# Main_Sch.net
KiCad netlist of a schematic drawn in Altium Designer
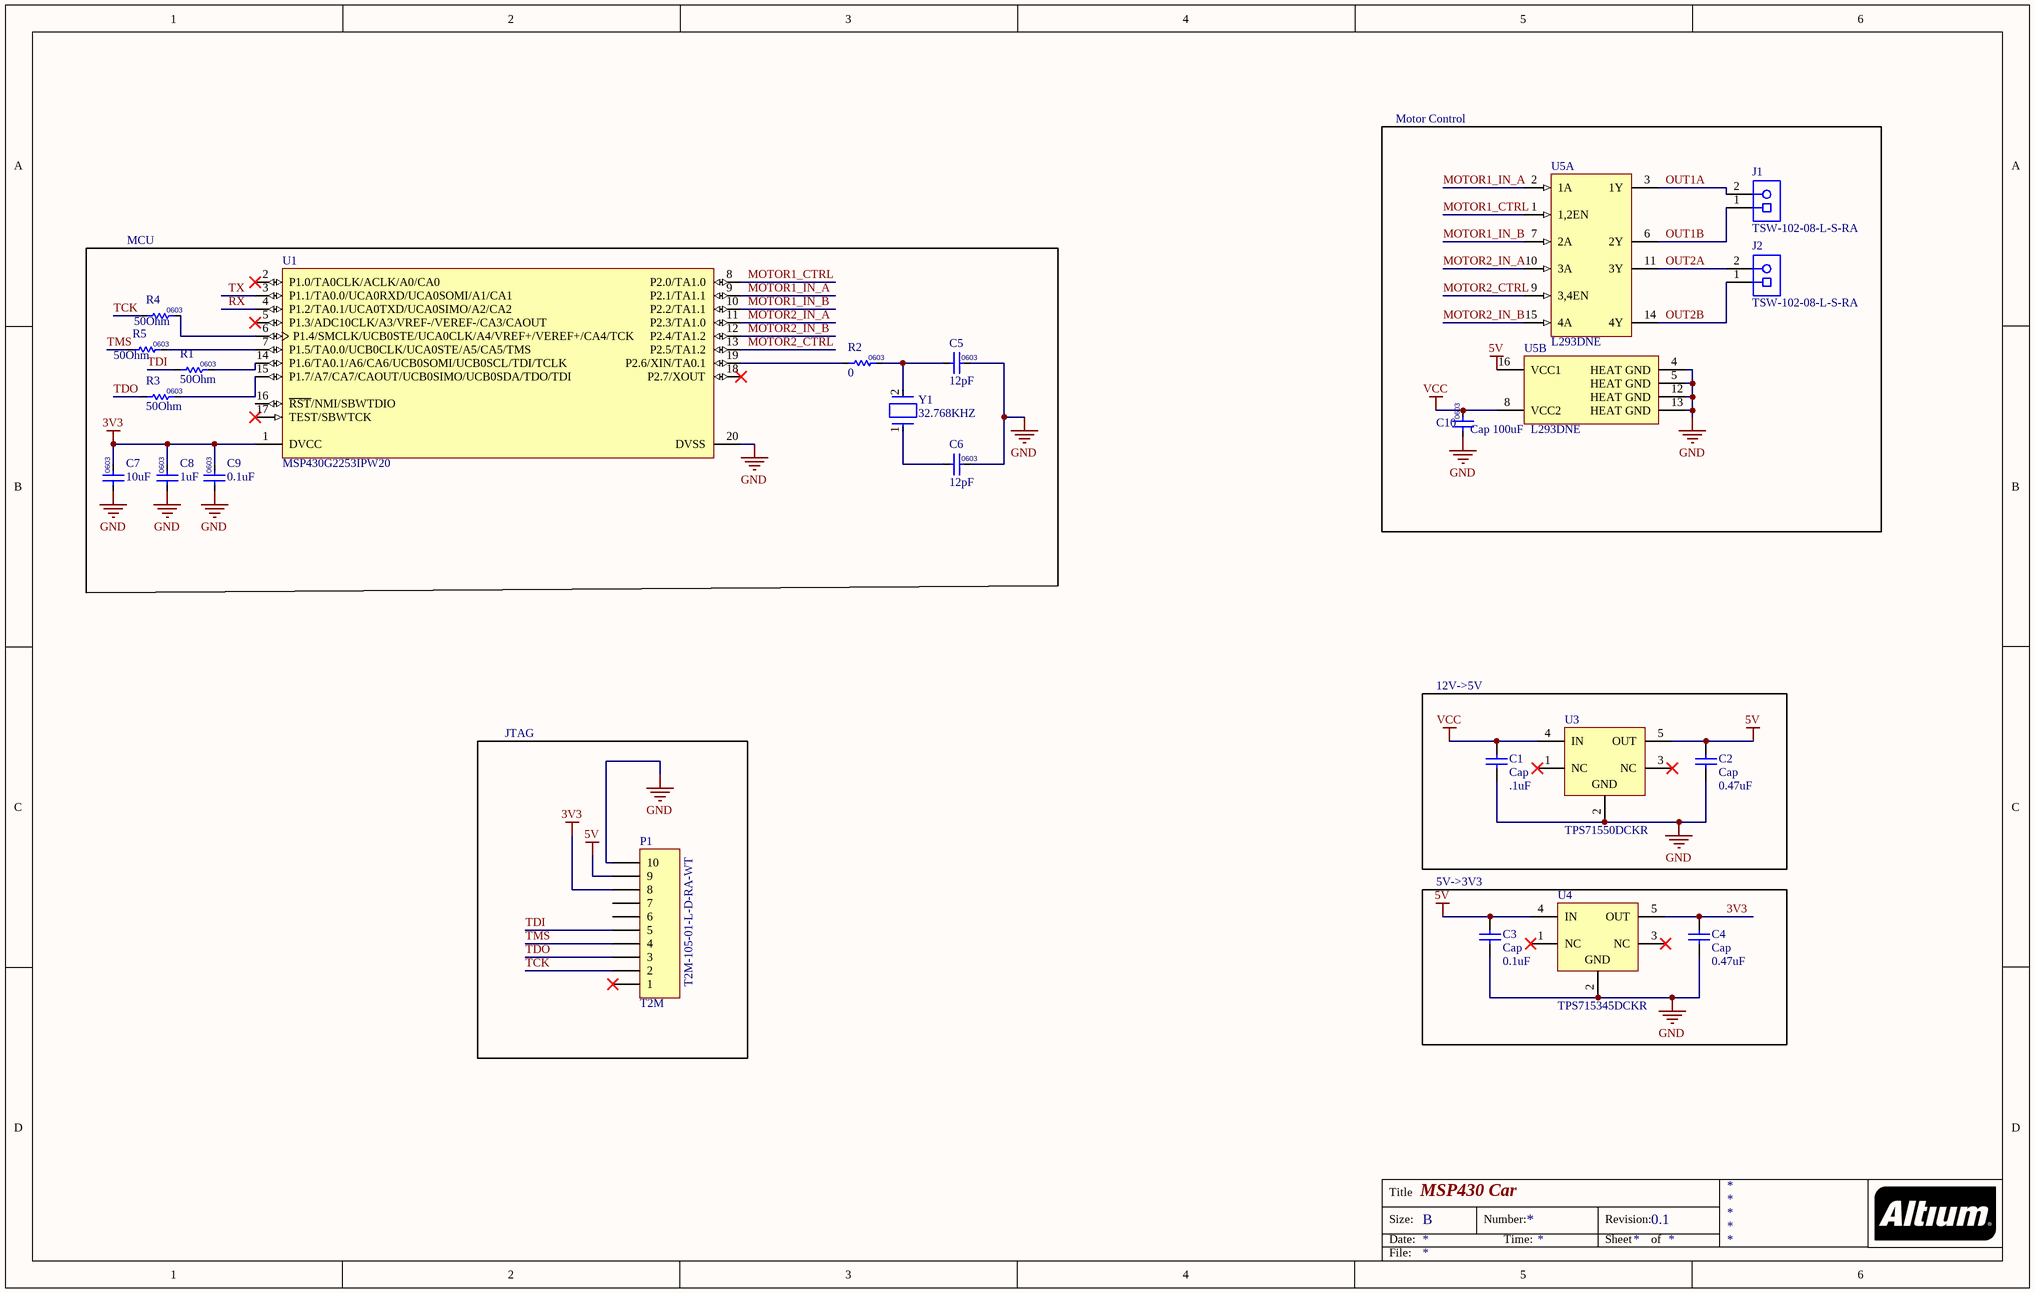
[diagram p0: Main_Sch.SchDoc]

(export (version "E")
  (design (tool "Eeschema 10.0.6"))
  (components
    (comp (ref "C1")
      (value "Cap")
      (footprint "RAD-0.3")
      (description "Capacitor")
      (fields (field (name "ALTIUM_VALUE") ".1uF") (field (name "PUBLISHER") "Altium Limited"))
      (libsource (lib "Miscellaneous Devices") (part "Cap"))
    )
    (comp (ref "C2")
      (value "Cap")
      (footprint "RAD-0.3")
      (description "Capacitor")
      (fields (field (name "ALTIUM_VALUE") "0.47uF") (field (name "PUBLISHER") "Altium Limited"))
      (libsource (lib "Miscellaneous Devices") (part "Cap"))
    )
    (comp (ref "C3")
      (value "Cap")
      (footprint "RAD-0.3")
      (description "Capacitor")
      (fields (field (name "ALTIUM_VALUE") "0.1uF") (field (name "PUBLISHER") "Altium Limited"))
      (libsource (lib "Miscellaneous Devices") (part "Cap"))
    )
    (comp (ref "C4")
      (value "Cap")
      (footprint "RAD-0.3")
      (description "Capacitor")
      (fields (field (name "ALTIUM_VALUE") "0.47uF") (field (name "PUBLISHER") "Altium Limited"))
      (libsource (lib "Miscellaneous Devices") (part "Cap"))
    )
    (comp (ref "C5")
      (value "12pF")
      (footprint "FP-CC0603-DA-IPC_B")
      (fields (field (name "VOLTAGE") "50V") (field (name "TOLERANCE") "5%"))
      (libsource (lib "University of Wisconsin Formula FSAE") (part "0603 ceramic cap"))
    )
    (comp (ref "C6")
      (value "12pF")
      (footprint "FP-CC0603-DA-IPC_B")
      (fields (field (name "VOLTAGE") "50V") (field (name "TOLERANCE") "5%"))
      (libsource (lib "University of Wisconsin Formula FSAE") (part "0603 ceramic cap"))
    )
    (comp (ref "C7")
      (value "10uF")
      (footprint "FP-CC0603-DA-IPC_B")
      (fields (field (name "VOLTAGE") "50V") (field (name "TOLERANCE") "5%"))
      (libsource (lib "University of Wisconsin Formula FSAE") (part "0603 ceramic cap"))
    )
    (comp (ref "C8")
      (value "1uF")
      (footprint "FP-CC0603-DA-IPC_B")
      (fields (field (name "VOLTAGE") "50V") (field (name "TOLERANCE") "5%"))
      (libsource (lib "University of Wisconsin Formula FSAE") (part "0603 ceramic cap"))
    )
    (comp (ref "C9")
      (value "0.1uF")
      (footprint "FP-CC0603-DA-IPC_B")
      (fields (field (name "VOLTAGE") "50V") (field (name "TOLERANCE") "5%"))
      (libsource (lib "University of Wisconsin Formula FSAE") (part "0603 ceramic cap"))
    )
    (comp (ref "C10")
      (value "Cap 100uF")
      (footprint "FP-CC0603-DA-IPC_B")
      (fields (field (name "VOLTAGE") "50V") (field (name "TOLERANCE") "5%"))
      (libsource (lib "University of Wisconsin Formula FSAE") (part "0603 ceramic cap"))
    )
    (comp (ref "J1")
      (value "TSW-102-08-L-S-RA")
      (footprint "SMTC-TSW-102-08-X-S-RA_overlay")
      (libsource (lib "University of Wisconsin Formula FSAE") (part "90 Degree Connector"))
    )
    (comp (ref "J2")
      (value "TSW-102-08-L-S-RA")
      (footprint "SMTC-TSW-102-08-X-S-RA_overlay")
      (libsource (lib "University of Wisconsin Formula FSAE") (part "90 Degree Connector"))
    )
    (comp (ref "P1")
      (value "T2M")
      (footprint "T2M-105-01-L-D-RA-WT")
      (description "Header, 10-Pin")
      (fields
        (field (name "MANUFACTURER") "Samtec")
        (field (name "MANUFACTURER PART NUMBER") "T2M-105-01-L-D-RA-WT")
      )
      (libsource (lib "Miscellaneous Connectors") (part "Header 10"))
    )
    (comp (ref "R1")
      (value "50Ohm")
      (footprint "Res0603-type-1")
      (description "Fixed Resistor, Metal Film, 0.1W, 15000ohm, 75V, 0.5% +/-Tol, 25ppm/Cel, Surface Mount, 0603")
      (fields (field (name "POWER") "100mW") (field (name "TOLERANCE") "0.5%"))
      (libsource (lib "University of Wisconsin Formula FSAE") (part "RES 0603"))
    )
    (comp (ref "R2")
      (value "0")
      (footprint "Res0603-type-1")
      (description "Fixed Resistor, Metal Film, 0.1W, 15000ohm, 75V, 0.5% +/-Tol, 25ppm/Cel, Surface Mount, 0603")
      (fields (field (name "POWER") "100mW") (field (name "TOLERANCE") "0.5%"))
      (libsource (lib "University of Wisconsin Formula FSAE") (part "RES 0603"))
    )
    (comp (ref "R3")
      (value "50Ohm")
      (footprint "Res0603-type-1")
      (description "Fixed Resistor, Metal Film, 0.1W, 15000ohm, 75V, 0.5% +/-Tol, 25ppm/Cel, Surface Mount, 0603")
      (fields (field (name "POWER") "100mW") (field (name "TOLERANCE") "0.5%"))
      (libsource (lib "University of Wisconsin Formula FSAE") (part "RES 0603"))
    )
    (comp (ref "R4")
      (value "50Ohm")
      (footprint "Res0603-type-1")
      (description "Fixed Resistor, Metal Film, 0.1W, 15000ohm, 75V, 0.5% +/-Tol, 25ppm/Cel, Surface Mount, 0603")
      (fields (field (name "POWER") "100mW") (field (name "TOLERANCE") "0.5%"))
      (libsource (lib "University of Wisconsin Formula FSAE") (part "RES 0603"))
    )
    (comp (ref "R5")
      (value "50Ohm")
      (footprint "Res0603-type-1")
      (description "Fixed Resistor, Metal Film, 0.1W, 15000ohm, 75V, 0.5% +/-Tol, 25ppm/Cel, Surface Mount, 0603")
      (fields (field (name "POWER") "100mW") (field (name "TOLERANCE") "0.5%"))
      (libsource (lib "University of Wisconsin Formula FSAE") (part "RES 0603"))
    )
    (comp (ref "U1")
      (value "MSP430G2253IPW20")
      (footprint "PW0020A_M")
      (description "RISC Microcontroller, 16-Bit, FLASH, MSP430 CPU, 16MHz, CMOS, PDSO20")
      (libsource (lib "University of Wisconsin Formula FSAE") (part "TI-MSP430G2X53-20"))
    )
    (comp (ref "U3")
      (value "TPS71550DCKR")
      (footprint "DCK0005A_N")
      (fields (field (name "MANUFACTURER") "Texas Instruments"))
      (libsource (lib "MSP430 Car") (part "CMP-0394-00921-2"))
    )
    (comp (ref "U4")
      (value "TPS715345DCKR")
      (footprint "DCK0005A_N")
      (fields (field (name "MANUFACTURER") "Texas Instruments"))
      (libsource (lib "MSP430 Car") (part "CMP-0394-00919-2"))
    )
    (comp (ref "U5")
      (value "L293DNE")
      (footprint "NE0016A")
      (fields (field (name "TOLERANCE") "10%"))
      (libsource (lib "MSP430 Car") (part "CMP-1685-00015-1"))
    )
    (comp (ref "Y1")
      (value "32.768KHZ")
      (footprint "FP-NX2012SA-MFG")
      (description "Crystal 32.768KHZ 7PF SMD")
      (libsource (lib "University of Wisconsin Formula FSAE") (part "c23a69dc6c9e2f18f2079038eb95dd1"))
    )
  )
  (nets
    (net (code "1") (name "/MOTOR1_CTRL") (class "Default")
      (node (ref "U1") (pin "8") (pinfunction "P2.0/TA1.0_8") (pintype "bidirectional"))
      (node (ref "U5") (pin "1") (pinfunction "1,2EN_1") (pintype "input"))
    )
    (net (code "2") (name "/MOTOR1_IN_A") (class "Default")
      (node (ref "U1") (pin "9") (pinfunction "P2.1/TA1.1_9") (pintype "bidirectional"))
      (node (ref "U5") (pin "2") (pinfunction "1A_2") (pintype "input"))
    )
    (net (code "3") (name "/MOTOR1_IN_B") (class "Default")
      (node (ref "U1") (pin "10") (pinfunction "P2.2/TA1.1_10") (pintype "bidirectional"))
      (node (ref "U5") (pin "7") (pinfunction "2A_7") (pintype "input"))
    )
    (net (code "4") (name "/MOTOR2_CTRL") (class "Default")
      (node (ref "U1") (pin "13") (pinfunction "P2.5/TA1.2_13") (pintype "bidirectional"))
      (node (ref "U5") (pin "9") (pinfunction "3,4EN_9") (pintype "input"))
    )
    (net (code "5") (name "/MOTOR2_IN_A") (class "Default")
      (node (ref "U1") (pin "11") (pinfunction "P2.3/TA1.0_11") (pintype "bidirectional"))
      (node (ref "U5") (pin "10") (pinfunction "3A_10") (pintype "input"))
    )
    (net (code "6") (name "/MOTOR2_IN_B") (class "Default")
      (node (ref "U1") (pin "12") (pinfunction "P2.4/TA1.2_12") (pintype "bidirectional"))
      (node (ref "U5") (pin "15") (pinfunction "4A_15") (pintype "input"))
    )
    (net (code "7") (name "/OUT1A") (class "Default")
      (node (ref "J1") (pin "2") (pinfunction "2_2") (pintype "passive"))
      (node (ref "U5") (pin "3") (pinfunction "1Y_3") (pintype "tri_state"))
    )
    (net (code "8") (name "/OUT1B") (class "Default")
      (node (ref "J1") (pin "1") (pinfunction "1_1") (pintype "passive"))
      (node (ref "U5") (pin "6") (pinfunction "2Y_6") (pintype "tri_state"))
    )
    (net (code "9") (name "/OUT2A") (class "Default")
      (node (ref "J2") (pin "2") (pinfunction "2_2") (pintype "passive"))
      (node (ref "U5") (pin "11") (pinfunction "3Y_11") (pintype "tri_state"))
    )
    (net (code "10") (name "/OUT2B") (class "Default")
      (node (ref "J2") (pin "1") (pinfunction "1_1") (pintype "passive"))
      (node (ref "U5") (pin "14") (pinfunction "4Y_14") (pintype "tri_state"))
    )
    (net (code "11") (name "/RX") (class "Default")
      (node (ref "U1") (pin "4") (pinfunction "P1.2/TA0.1/UCA0TXD/UCA0SIMO/A2/CA2_4") (pintype "bidirectional"))
    )
    (net (code "12") (name "/TCK") (class "Default")
      (node (ref "P1") (pin "2") (pinfunction "2_2") (pintype "passive"))
      (node (ref "R4") (pin "1") (pinfunction "1_1") (pintype "passive"))
    )
    (net (code "13") (name "/TDI") (class "Default")
      (node (ref "P1") (pin "5") (pinfunction "5_5") (pintype "passive"))
      (node (ref "R1") (pin "1") (pinfunction "1_1") (pintype "passive"))
    )
    (net (code "14") (name "/TDO") (class "Default")
      (node (ref "P1") (pin "3") (pinfunction "3_3") (pintype "passive"))
      (node (ref "R3") (pin "1") (pinfunction "1_1") (pintype "passive"))
    )
    (net (code "15") (name "/TMS") (class "Default")
      (node (ref "P1") (pin "4") (pinfunction "4_4") (pintype "passive"))
      (node (ref "R5") (pin "1") (pinfunction "1_1") (pintype "passive"))
    )
    (net (code "16") (name "/TX") (class "Default")
      (node (ref "U1") (pin "3") (pinfunction "P1.1/TA0.0/UCA0RXD/UCA0SOMI/A1/CA1_3") (pintype "bidirectional"))
    )
    (net (code "17") (name "3V3") (class "Default")
      (node (ref "C4") (pin "2") (pinfunction "2_2") (pintype "passive"))
      (node (ref "C7") (pin "2") (pinfunction "2_2") (pintype "passive"))
      (node (ref "C8") (pin "2") (pinfunction "2_2") (pintype "passive"))
      (node (ref "C9") (pin "2") (pinfunction "2_2") (pintype "passive"))
      (node (ref "P1") (pin "8") (pinfunction "8_8") (pintype "passive"))
      (node (ref "U1") (pin "1") (pinfunction "DVCC_1") (pintype "power_in"))
      (node (ref "U4") (pin "5") (pinfunction "OUT_5") (pintype "power_in"))
    )
    (net (code "18") (name "5V") (class "Default")
      (node (ref "C2") (pin "2") (pinfunction "2_2") (pintype "passive"))
      (node (ref "C3") (pin "2") (pinfunction "2_2") (pintype "passive"))
      (node (ref "P1") (pin "9") (pinfunction "9_9") (pintype "passive"))
      (node (ref "U3") (pin "5") (pinfunction "OUT_5") (pintype "power_in"))
      (node (ref "U4") (pin "4") (pinfunction "IN_4") (pintype "power_in"))
      (node (ref "U5") (pin "16") (pinfunction "VCC1_16") (pintype "power_in"))
    )
    (net (code "19") (name "GND") (class "Default")
      (node (ref "C1") (pin "1") (pinfunction "1_1") (pintype "passive"))
      (node (ref "C10") (pin "1") (pinfunction "1_1") (pintype "passive"))
      (node (ref "C2") (pin "1") (pinfunction "1_1") (pintype "passive"))
      (node (ref "C3") (pin "1") (pinfunction "1_1") (pintype "passive"))
      (node (ref "C4") (pin "1") (pinfunction "1_1") (pintype "passive"))
      (node (ref "C5") (pin "2") (pinfunction "2_2") (pintype "passive"))
      (node (ref "C6") (pin "2") (pinfunction "2_2") (pintype "passive"))
      (node (ref "C7") (pin "1") (pinfunction "1_1") (pintype "passive"))
      (node (ref "C8") (pin "1") (pinfunction "1_1") (pintype "passive"))
      (node (ref "C9") (pin "1") (pinfunction "1_1") (pintype "passive"))
      (node (ref "P1") (pin "10") (pinfunction "10_10") (pintype "passive"))
      (node (ref "U1") (pin "20") (pinfunction "DVSS_20") (pintype "power_in"))
      (node (ref "U3") (pin "2") (pinfunction "GND_2") (pintype "power_in"))
      (node (ref "U4") (pin "2") (pinfunction "GND_2") (pintype "power_in"))
      (node (ref "U5") (pin "12") (pinfunction "HEAT_GND_12") (pintype "power_in"))
      (node (ref "U5") (pin "13") (pinfunction "HEAT_GND_13") (pintype "power_in"))
      (node (ref "U5") (pin "4") (pinfunction "HEAT_GND_4") (pintype "power_in"))
      (node (ref "U5") (pin "5") (pinfunction "HEAT_GND_5") (pintype "power_in"))
    )
    (net (code "20") (name "Net-(C5-Pad1)") (class "Default")
      (node (ref "C5") (pin "1") (pinfunction "1_1") (pintype "passive"))
      (node (ref "R2") (pin "2") (pinfunction "2_2") (pintype "passive"))
      (node (ref "Y1") (pin "2") (pinfunction "2_2") (pintype "passive"))
    )
    (net (code "21") (name "Net-(C6-Pad1)") (class "Default")
      (node (ref "C6") (pin "1") (pinfunction "1_1") (pintype "passive"))
      (node (ref "Y1") (pin "1") (pinfunction "1_1") (pintype "passive"))
    )
    (net (code "22") (name "Net-(U1-P1.4{slash}SMCLK{slash}UCB0STE{slash}UCA0CLK{slash}A4{slash}VREF+{slash}VEREF+{slash}CA4{slash}TCK)") (class "Default")
      (node (ref "R4") (pin "2") (pinfunction "2_2") (pintype "passive"))
      (node (ref "U1") (pin "6") (pinfunction "P1.4/SMCLK/UCB0STE/UCA0CLK/A4/VREF+/VEREF+/CA4/TCK_6") (pintype "bidirectional"))
    )
    (net (code "23") (name "Net-(U1-P1.5{slash}TA0.0{slash}UCB0CLK{slash}UCA0STE{slash}A5{slash}CA5{slash}TMS)") (class "Default")
      (node (ref "R5") (pin "2") (pinfunction "2_2") (pintype "passive"))
      (node (ref "U1") (pin "7") (pinfunction "P1.5/TA0.0/UCB0CLK/UCA0STE/A5/CA5/TMS_7") (pintype "bidirectional"))
    )
    (net (code "24") (name "Net-(U1-P1.6{slash}TA0.1{slash}A6{slash}CA6{slash}UCB0SOMI{slash}UCB0SCL{slash}TDI{slash}TCLK)") (class "Default")
      (node (ref "R1") (pin "2") (pinfunction "2_2") (pintype "passive"))
      (node (ref "U1") (pin "14") (pinfunction "P1.6/TA0.1/A6/CA6/UCB0SOMI/UCB0SCL/TDI/TCLK_14") (pintype "bidirectional"))
    )
    (net (code "25") (name "Net-(U1-P1.7{slash}A7{slash}CA7{slash}CAOUT{slash}UCB0SIMO{slash}UCB0SDA{slash}TDO{slash}TDI)") (class "Default")
      (node (ref "R3") (pin "2") (pinfunction "2_2") (pintype "passive"))
      (node (ref "U1") (pin "15") (pinfunction "P1.7/A7/CA7/CAOUT/UCB0SIMO/UCB0SDA/TDO/TDI_15") (pintype "bidirectional"))
    )
    (net (code "26") (name "Net-(U1-P2.6{slash}XIN{slash}TA0.1)") (class "Default")
      (node (ref "R2") (pin "1") (pinfunction "1_1") (pintype "passive"))
      (node (ref "U1") (pin "19") (pinfunction "P2.6/XIN/TA0.1_19") (pintype "bidirectional"))
    )
    (net (code "27") (name "VCC") (class "Default")
      (node (ref "C1") (pin "2") (pinfunction "2_2") (pintype "passive"))
      (node (ref "C10") (pin "2") (pinfunction "2_2") (pintype "passive"))
      (node (ref "U3") (pin "4") (pinfunction "IN_4") (pintype "power_in"))
      (node (ref "U5") (pin "8") (pinfunction "VCC2_8") (pintype "power_in"))
    )
    (net (code "28") (name "unconnected-(P1-Pad1)") (class "Default")
      (node (ref "P1") (pin "1") (pinfunction "1_1") (pintype "passive+no_connect"))
    )
    (net (code "29") (name "unconnected-(P1-Pad6)") (class "Default")
      (node (ref "P1") (pin "6") (pinfunction "6_6") (pintype "passive"))
    )
    (net (code "30") (name "unconnected-(P1-Pad7)") (class "Default")
      (node (ref "P1") (pin "7") (pinfunction "7_7") (pintype "passive"))
    )
    (net (code "31") (name "unconnected-(U1-P1.0{slash}TA0CLK{slash}ACLK{slash}A0{slash}CA0-Pad2)") (class "Default")
      (node (ref "U1") (pin "2") (pinfunction "P1.0/TA0CLK/ACLK/A0/CA0_2") (pintype "bidirectional+no_connect"))
    )
    (net (code "32") (name "unconnected-(U1-P1.3{slash}ADC10CLK{slash}A3{slash}VREF-{slash}VEREF-{slash}CA3{slash}CAOUT-Pad5)") (class "Default")
      (node (ref "U1") (pin "5") (pinfunction "P1.3/ADC10CLK/A3/VREF-/VEREF-/CA3/CAOUT_5") (pintype "bidirectional+no_connect"))
    )
    (net (code "33") (name "unconnected-(U1-P2.7{slash}XOUT-Pad18)") (class "Default")
      (node (ref "U1") (pin "18") (pinfunction "P2.7/XOUT_18") (pintype "bidirectional+no_connect"))
    )
    (net (code "34") (name "unconnected-(U1-TEST{slash}SBWTCK-Pad17)") (class "Default")
      (node (ref "U1") (pin "17") (pinfunction "TEST/SBWTCK_17") (pintype "input+no_connect"))
    )
    (net (code "35") (name "unconnected-(U1-~{RST}{slash}NMI{slash}SBWTDIO-Pad16)") (class "Default")
      (node (ref "U1") (pin "16") (pinfunction "~{RST}/NMI/SBWTDIO_16") (pintype "bidirectional"))
    )
    (net (code "36") (name "unconnected-(U3-NC-Pad1)") (class "Default")
      (node (ref "U3") (pin "1") (pinfunction "NC_1") (pintype "passive+no_connect"))
    )
    (net (code "37") (name "unconnected-(U3-NC-Pad3)") (class "Default")
      (node (ref "U3") (pin "3") (pinfunction "NC_3") (pintype "passive+no_connect"))
    )
    (net (code "38") (name "unconnected-(U4-NC-Pad1)") (class "Default")
      (node (ref "U4") (pin "1") (pinfunction "NC_1") (pintype "passive+no_connect"))
    )
    (net (code "39") (name "unconnected-(U4-NC-Pad3)") (class "Default")
      (node (ref "U4") (pin "3") (pinfunction "NC_3") (pintype "passive+no_connect"))
    )
  )
)
